# LDO_Reg.net
KiCad netlist of a schematic drawn in Altium Designer
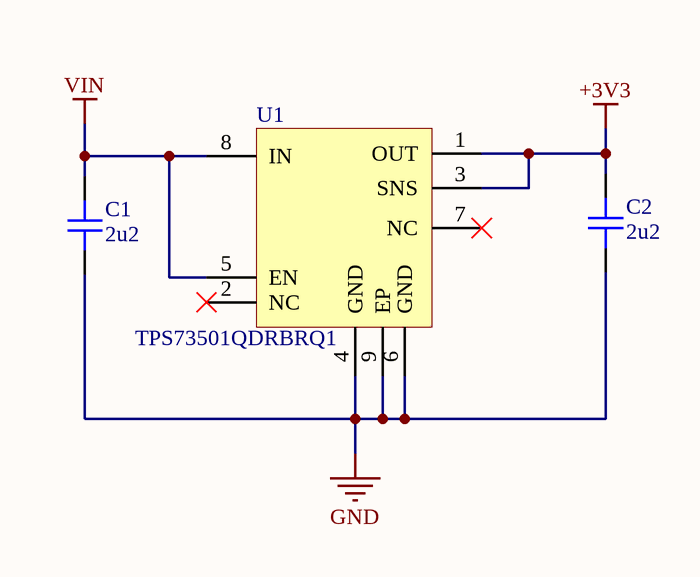
[diagram p0: LDO_Reg.SchDoc]

(export (version "E")
  (design (tool "Eeschema 10.0.6"))
  (components
    (comp (ref "C1")
      (value "2u2")
      (footprint "CAP_0402")
      (description "Capacitor SMD 0402 16V")
      (libsource (lib "Schematic-Lib-Zhrzkn") (part "CAP_0402_16V"))
    )
    (comp (ref "C2")
      (value "2u2")
      (footprint "CAP_0402")
      (description "Capacitor SMD 0402 16V")
      (libsource (lib "Schematic-Lib-Zhrzkn") (part "CAP_0402_16V"))
    )
    (comp (ref "U1")
      (value "TPS73501QDRBRQ1")
      (footprint "VSON-8")
      (description "LDO Regulator Pos 1.25V to 6V 0.5A Automotive 8-Pin VSON EP T/R")
      (fields (field (name "MANUFACTURER") "Texas Instruments"))
      (libsource (lib "Schematic-Lib-Zhrzkn") (part "TPS73501QDRBRQ1"))
    )
  )
  (nets
    (net (code "1") (name "+3V3") (class "Default")
      (node (ref "C2") (pin "2") (pinfunction "2_2") (pintype "passive"))
      (node (ref "U1") (pin "1") (pinfunction "OUT_1") (pintype "passive"))
      (node (ref "U1") (pin "3") (pinfunction "SNS_3") (pintype "passive"))
    )
    (net (code "2") (name "GND") (class "Default")
      (node (ref "C1") (pin "1") (pinfunction "1_1") (pintype "passive"))
      (node (ref "C2") (pin "1") (pinfunction "1_1") (pintype "passive"))
      (node (ref "U1") (pin "4") (pinfunction "GND_4") (pintype "passive"))
      (node (ref "U1") (pin "6") (pinfunction "GND_6") (pintype "passive"))
      (node (ref "U1") (pin "9") (pinfunction "EP_9") (pintype "passive"))
    )
    (net (code "3") (name "VIN") (class "Default")
      (node (ref "C1") (pin "2") (pinfunction "2_2") (pintype "passive"))
      (node (ref "U1") (pin "5") (pinfunction "EN_5") (pintype "power_in"))
      (node (ref "U1") (pin "8") (pinfunction "IN_8") (pintype "passive"))
    )
    (net (code "4") (name "unconnected-(U1-NC-Pad2)") (class "Default")
      (node (ref "U1") (pin "2") (pinfunction "NC_2") (pintype "power_in+no_connect"))
    )
    (net (code "5") (name "unconnected-(U1-NC-Pad7)") (class "Default")
      (node (ref "U1") (pin "7") (pinfunction "NC_7") (pintype "passive+no_connect"))
    )
  )
)
